# Function-Generator.net
KiCad netlist of a schematic drawn in Altium Designer
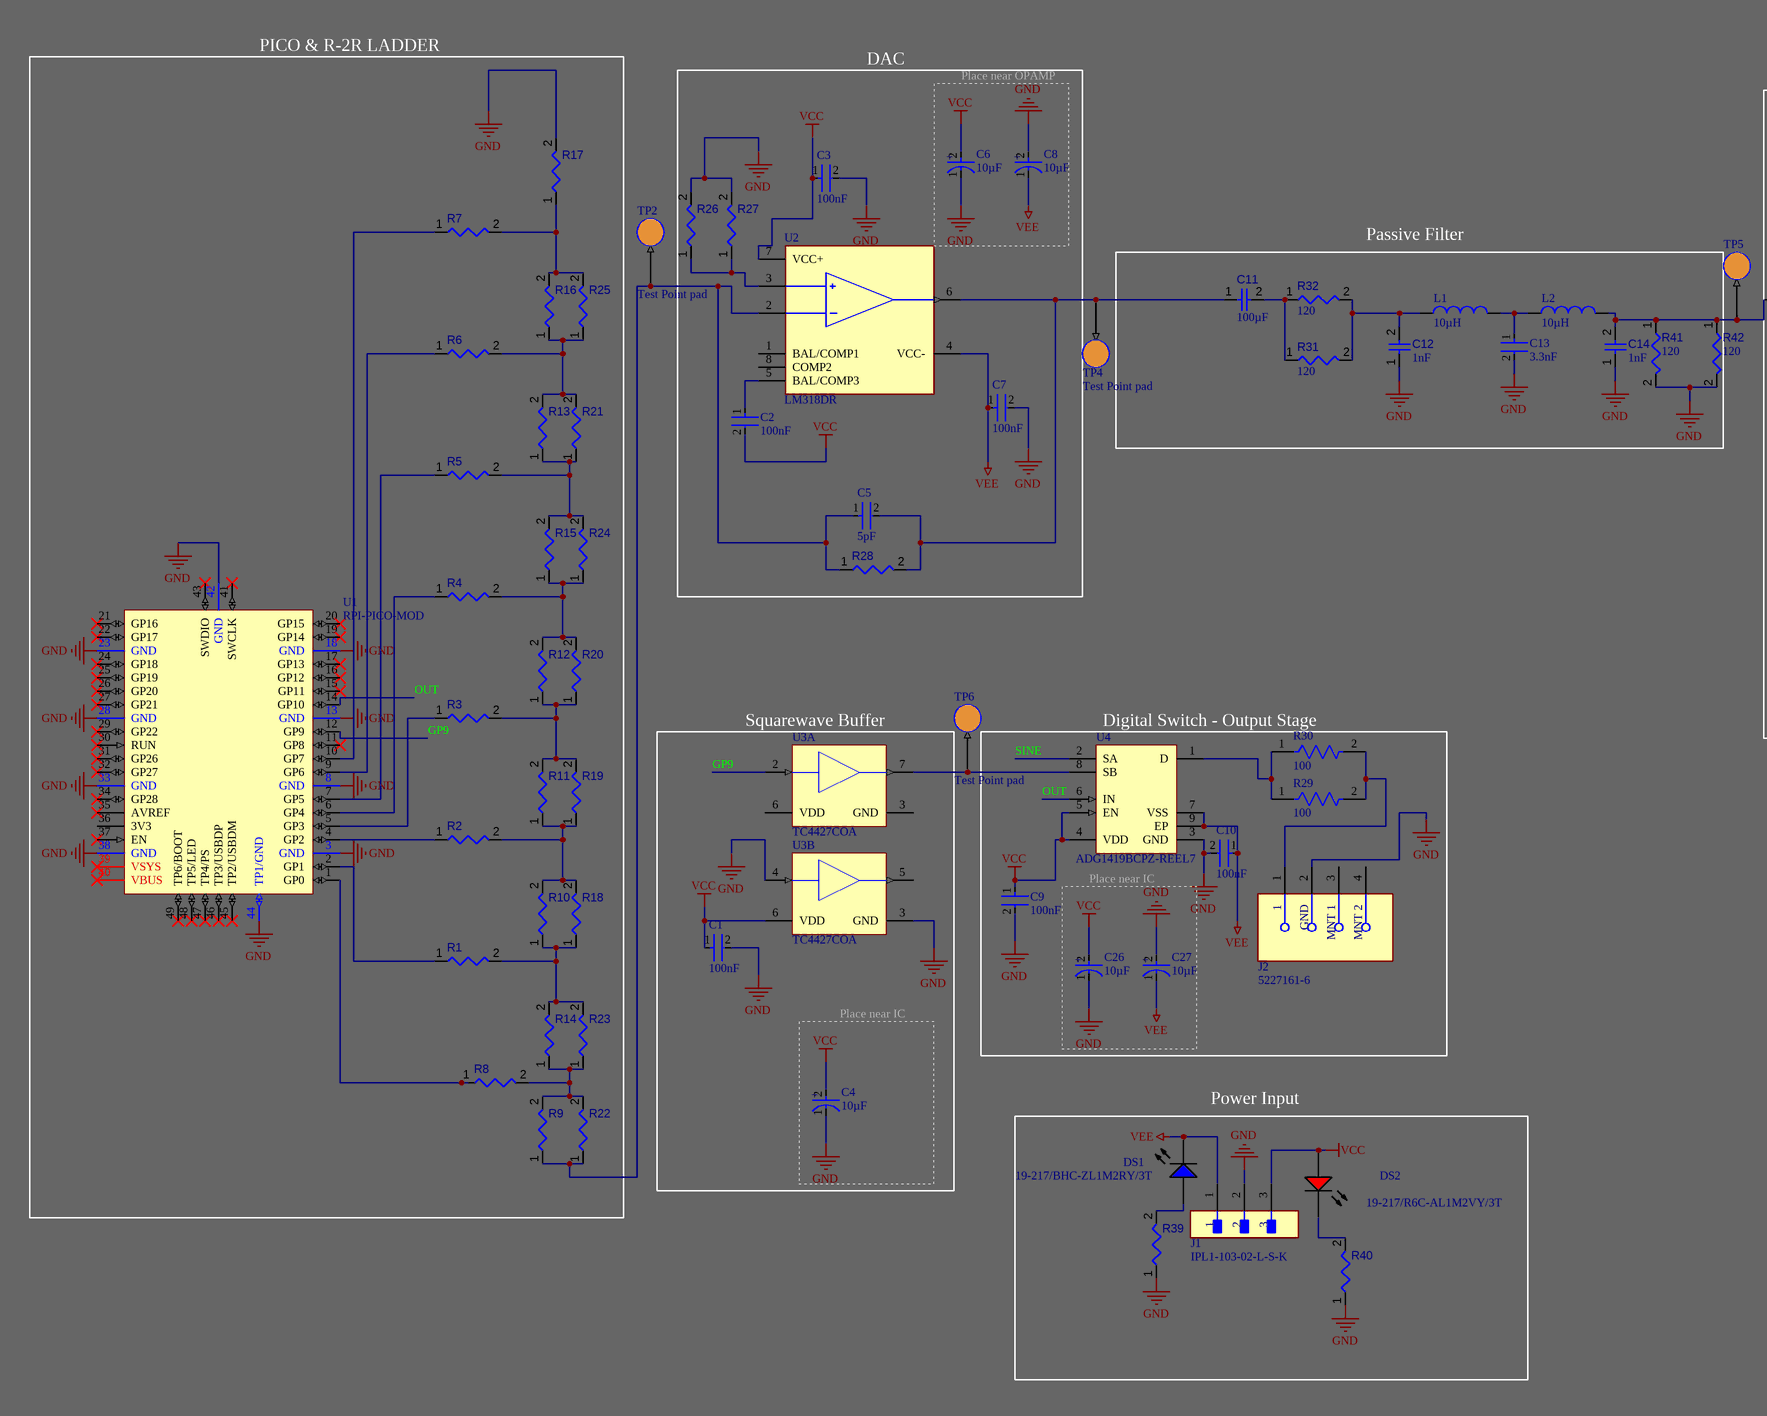
[diagram p0: Function-Generator.SchDoc, left]
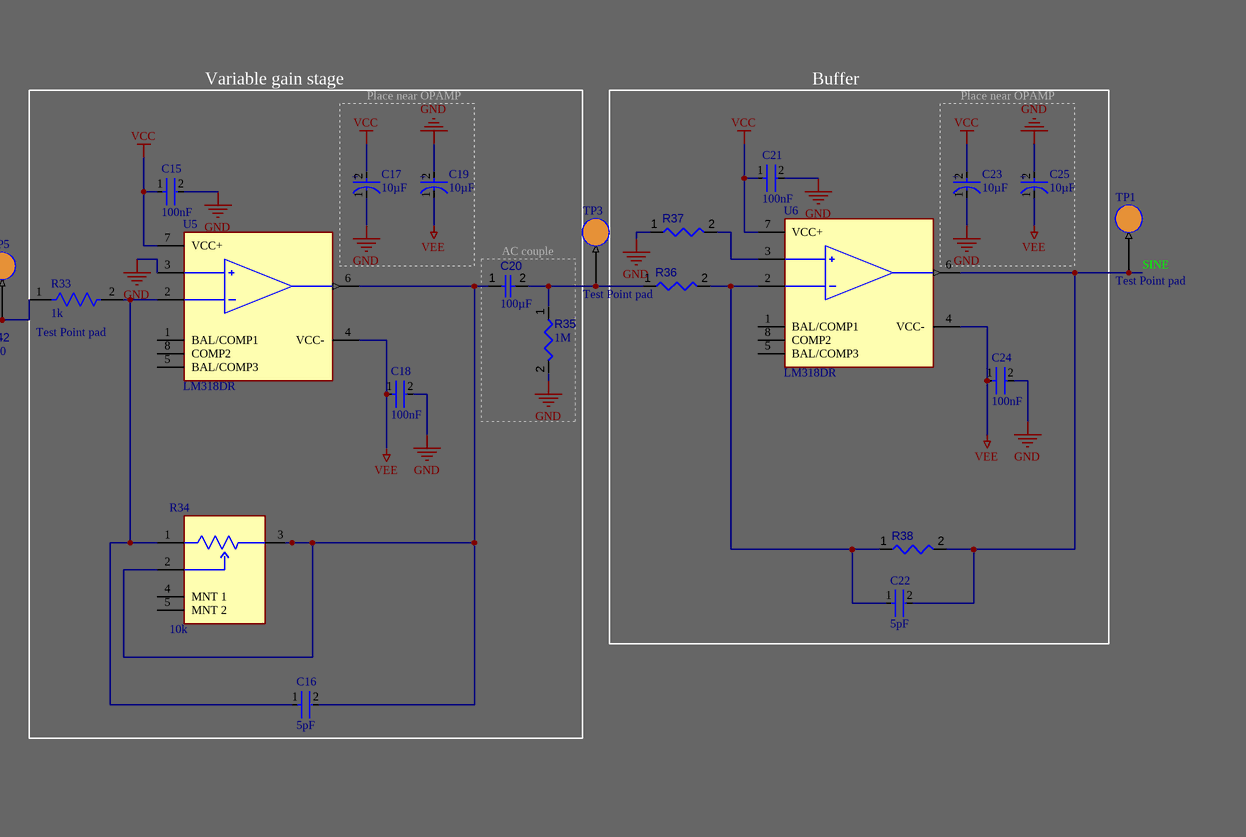
[diagram p1: Function-Generator.SchDoc, right]

(export (version "E")
  (design (tool "Eeschema 10.0.6"))
  (components
    (comp (ref "C1")
      (value "100nF")
      (footprint "FP-CC0805-0_85-IPC_A")
      (description "100V 100nF X7R 卤10% 0805 Multilayer Ceramic Capacitors MLCC - SMD/SMT ROHS")
      (fields (field (name "VOLTAGE") "25V") (field (name "TOLERANCE") "10%"))
      (libsource (lib "Lambros25") (part "11868f565c42a9108669ba33697ecf6"))
    )
    (comp (ref "C2")
      (value "100nF")
      (footprint "FP-CC0805-0_85-IPC_A")
      (description "100V 100nF X7R 卤10% 0805 Multilayer Ceramic Capacitors MLCC - SMD/SMT ROHS")
      (fields (field (name "VOLTAGE") "25V") (field (name "TOLERANCE") "10%"))
      (libsource (lib "Lambros25") (part "11868f565c42a9108669ba33697ecf6"))
    )
    (comp (ref "C3")
      (value "100nF")
      (footprint "FP-CC0805-0_85-IPC_A")
      (description "100V 100nF X7R 卤10% 0805 Multilayer Ceramic Capacitors MLCC - SMD/SMT ROHS")
      (fields (field (name "VOLTAGE") "25V") (field (name "TOLERANCE") "10%"))
      (libsource (lib "Lambros25") (part "11868f565c42a9108669ba33697ecf6"))
    )
    (comp (ref "C4")
      (value "10µF")
      (footprint "FP-FTB-MFG")
      (description "Radial Can - SMD ALUMINUM ELECTROLYTIC CAPACITOR FT 50V 10muF ±20% 0.157Dia 4.00mm")
      (fields (field (name "VOLTAGE") "50V") (field (name "TOLERANCE") "20%"))
      (libsource (lib "Lambros25") (part "a00bbbee19879c290e62620ae7e47b1"))
    )
    (comp (ref "C5")
      (value "5pF")
      (footprint "FP-GCH188-0_1-e0_2_0_5-IPC_A")
      (fields (field (name "JLCPCB PART #") "C1673") (field (name "Comment") "GCH1885C2A5R0CE01J"))
      (libsource (lib "Lambros25") (part "b4654b650e69147ec39a6b967a45e02"))
    )
    (comp (ref "C6")
      (value "10µF")
      (footprint "FP-FTB-MFG")
      (description "Radial Can - SMD ALUMINUM ELECTROLYTIC CAPACITOR FT 50V 10muF ±20% 0.157Dia 4.00mm")
      (fields (field (name "VOLTAGE") "50V") (field (name "TOLERANCE") "20%"))
      (libsource (lib "Lambros25") (part "a00bbbee19879c290e62620ae7e47b1"))
    )
    (comp (ref "C7")
      (value "100nF")
      (footprint "FP-CC0805-0_85-IPC_A")
      (description "100V 100nF X7R 卤10% 0805 Multilayer Ceramic Capacitors MLCC - SMD/SMT ROHS")
      (fields (field (name "VOLTAGE") "25V") (field (name "TOLERANCE") "10%"))
      (libsource (lib "Lambros25") (part "11868f565c42a9108669ba33697ecf6"))
    )
    (comp (ref "C8")
      (value "10µF")
      (footprint "FP-FTB-MFG")
      (description "Radial Can - SMD ALUMINUM ELECTROLYTIC CAPACITOR FT 50V 10muF ±20% 0.157Dia 4.00mm")
      (fields (field (name "VOLTAGE") "50V") (field (name "TOLERANCE") "20%"))
      (libsource (lib "Lambros25") (part "a00bbbee19879c290e62620ae7e47b1"))
    )
    (comp (ref "C9")
      (value "100nF")
      (footprint "FP-CC0805-0_85-IPC_A")
      (description "100V 100nF X7R 卤10% 0805 Multilayer Ceramic Capacitors MLCC - SMD/SMT ROHS")
      (fields (field (name "VOLTAGE") "25V") (field (name "TOLERANCE") "10%"))
      (libsource (lib "Lambros25") (part "11868f565c42a9108669ba33697ecf6"))
    )
    (comp (ref "C10")
      (value "100nF")
      (footprint "FP-CC0805-0_85-IPC_A")
      (description "100V 100nF X7R 卤10% 0805 Multilayer Ceramic Capacitors MLCC - SMD/SMT ROHS")
      (fields (field (name "VOLTAGE") "25V") (field (name "TOLERANCE") "10%"))
      (libsource (lib "Lambros25") (part "11868f565c42a9108669ba33697ecf6"))
    )
    (comp (ref "C11")
      (value "100µF")
      (footprint "CAPAE660650X800N")
      (description "Radial Can - SMD ALUMINUM ELECTROLYTIC CAPACITOR SEV 25V 100muF ±20% 0.248Dia 6.30mm")
      (fields (field (name "TOLERANCE") "20%") (field (name "JLCPCB PART #") "C3338"))
      (libsource (lib "Lambros25") (part "CAP-NP-2"))
    )
    (comp (ref "C12")
      (value "1nF")
      (footprint "Chip2PinSM127P600-8N")
      (description "1nF 50V C0G ±1% 0805 Multilayer Ceramic Capacitors MLCC - SMD/SMT ROHS")
      (fields (field (name "JLCPCB PART #") "C597356") (field (name "TOLERANCE") "10%"))
      (libsource (lib "Lambros25") (part "CAP-NP-2"))
    )
    (comp (ref "C13")
      (value "3.3nF")
      (footprint "FP-CL10-IPC_B")
      (description "50V 3.3nF C0G ±1% 0603 Multilayer Ceramic Capacitors MLCC - SMD/SMT ROHS")
      (fields (field (name "TOLERANCE") "1%") (field (name "VOLTAGE") "50V"))
      (libsource (lib "Lambros25") (part "02cd4be3c70576c341d710602a673aa"))
    )
    (comp (ref "C14")
      (value "1nF")
      (footprint "Chip2PinSM127P600-8N")
      (description "1nF 50V C0G ±1% 0805 Multilayer Ceramic Capacitors MLCC - SMD/SMT ROHS")
      (fields (field (name "JLCPCB PART #") "C597356") (field (name "TOLERANCE") "10%"))
      (libsource (lib "Lambros25") (part "CAP-NP-2"))
    )
    (comp (ref "C15")
      (value "100nF")
      (footprint "FP-CC0805-0_85-IPC_A")
      (description "100V 100nF X7R 卤10% 0805 Multilayer Ceramic Capacitors MLCC - SMD/SMT ROHS")
      (fields (field (name "VOLTAGE") "25V") (field (name "TOLERANCE") "10%"))
      (libsource (lib "Lambros25") (part "11868f565c42a9108669ba33697ecf6"))
    )
    (comp (ref "C16")
      (value "5pF")
      (footprint "FP-GCH188-0_1-e0_2_0_5-IPC_A")
      (fields (field (name "JLCPCB PART #") "C1673") (field (name "Comment") "GCH1885C2A5R0CE01J"))
      (libsource (lib "Lambros25") (part "b4654b650e69147ec39a6b967a45e02"))
    )
    (comp (ref "C17")
      (value "10µF")
      (footprint "FP-FTB-MFG")
      (description "Radial Can - SMD ALUMINUM ELECTROLYTIC CAPACITOR FT 50V 10muF ±20% 0.157Dia 4.00mm")
      (fields (field (name "VOLTAGE") "50V") (field (name "TOLERANCE") "20%"))
      (libsource (lib "Lambros25") (part "a00bbbee19879c290e62620ae7e47b1"))
    )
    (comp (ref "C18")
      (value "100nF")
      (footprint "FP-CC0805-0_85-IPC_A")
      (description "100V 100nF X7R 卤10% 0805 Multilayer Ceramic Capacitors MLCC - SMD/SMT ROHS")
      (fields (field (name "VOLTAGE") "25V") (field (name "TOLERANCE") "10%"))
      (libsource (lib "Lambros25") (part "11868f565c42a9108669ba33697ecf6"))
    )
    (comp (ref "C19")
      (value "10µF")
      (footprint "FP-FTB-MFG")
      (description "Radial Can - SMD ALUMINUM ELECTROLYTIC CAPACITOR FT 50V 10muF ±20% 0.157Dia 4.00mm")
      (fields (field (name "VOLTAGE") "50V") (field (name "TOLERANCE") "20%"))
      (libsource (lib "Lambros25") (part "a00bbbee19879c290e62620ae7e47b1"))
    )
    (comp (ref "C20")
      (value "100µF")
      (footprint "CAPAE660650X800N")
      (description "Radial Can - SMD ALUMINUM ELECTROLYTIC CAPACITOR SEV 25V 100muF ±20% 0.248Dia 6.30mm")
      (fields (field (name "TOLERANCE") "20%") (field (name "JLCPCB PART #") "C3338"))
      (libsource (lib "Lambros25") (part "CAP-NP-2"))
    )
    (comp (ref "C21")
      (value "100nF")
      (footprint "FP-CC0805-0_85-IPC_A")
      (description "100V 100nF X7R 卤10% 0805 Multilayer Ceramic Capacitors MLCC - SMD/SMT ROHS")
      (fields (field (name "VOLTAGE") "25V") (field (name "TOLERANCE") "10%"))
      (libsource (lib "Lambros25") (part "11868f565c42a9108669ba33697ecf6"))
    )
    (comp (ref "C22")
      (value "5pF")
      (footprint "FP-GCH188-0_1-e0_2_0_5-IPC_A")
      (fields (field (name "JLCPCB PART #") "C1673") (field (name "Comment") "GCH1885C2A5R0CE01J"))
      (libsource (lib "Lambros25") (part "b4654b650e69147ec39a6b967a45e02"))
    )
    (comp (ref "C23")
      (value "10µF")
      (footprint "FP-FTB-MFG")
      (description "Radial Can - SMD ALUMINUM ELECTROLYTIC CAPACITOR FT 50V 10muF ±20% 0.157Dia 4.00mm")
      (fields (field (name "VOLTAGE") "50V") (field (name "TOLERANCE") "20%"))
      (libsource (lib "Lambros25") (part "a00bbbee19879c290e62620ae7e47b1"))
    )
    (comp (ref "C24")
      (value "100nF")
      (footprint "FP-CC0805-0_85-IPC_A")
      (description "100V 100nF X7R 卤10% 0805 Multilayer Ceramic Capacitors MLCC - SMD/SMT ROHS")
      (fields (field (name "VOLTAGE") "25V") (field (name "TOLERANCE") "10%"))
      (libsource (lib "Lambros25") (part "11868f565c42a9108669ba33697ecf6"))
    )
    (comp (ref "C25")
      (value "10µF")
      (footprint "FP-FTB-MFG")
      (description "Radial Can - SMD ALUMINUM ELECTROLYTIC CAPACITOR FT 50V 10muF ±20% 0.157Dia 4.00mm")
      (fields (field (name "VOLTAGE") "50V") (field (name "TOLERANCE") "20%"))
      (libsource (lib "Lambros25") (part "a00bbbee19879c290e62620ae7e47b1"))
    )
    (comp (ref "C26")
      (value "10µF")
      (footprint "FP-FTB-MFG")
      (description "Radial Can - SMD ALUMINUM ELECTROLYTIC CAPACITOR FT 50V 10muF ±20% 0.157Dia 4.00mm")
      (fields (field (name "VOLTAGE") "50V") (field (name "TOLERANCE") "20%"))
      (libsource (lib "Lambros25") (part "a00bbbee19879c290e62620ae7e47b1"))
    )
    (comp (ref "C27")
      (value "10µF")
      (footprint "FP-FTB-MFG")
      (description "Radial Can - SMD ALUMINUM ELECTROLYTIC CAPACITOR FT 50V 10muF ±20% 0.157Dia 4.00mm")
      (fields (field (name "VOLTAGE") "50V") (field (name "TOLERANCE") "20%"))
      (libsource (lib "Lambros25") (part "a00bbbee19879c290e62620ae7e47b1"))
    )
    (comp (ref "DS1")
      (value "19-217/BHC-ZL1M2RY/3T")
      (footprint "EVRL-0603-2_V")
      (description "Chip LED, Blue, 5 V, 25 mA, -40 to 85 degC, 2-Pin SMD (0603), RoHS, Tape and Reel")
      (fields (field (name "MANUFACTURER") "Everlight Electronics") (field (name "JLCPCB PART #") "C2288"))
      (libsource (lib "Lambros25") (part "LED-BLUE-AK-2"))
    )
    (comp (ref "DS2")
      (value "19-217/R6C-AL1M2VY/3T")
      (footprint "EVRL-0603-2_V")
      (description "Chip LED, Red, 5 V, 25 mA, -40 to 85 degC, 2-Pin SMD (0603), RoHS, Tape and Reel")
      (fields (field (name "MANUFACTURER") "Everlight Electronics") (field (name "JLCPCB PART #") "C2286"))
      (libsource (lib "Lambros25") (part "LED-RED-AK-2"))
    )
    (comp (ref "J1")
      (value "IPL1-103-02-L-S-K")
      (footprint "FP-IPL1-103-02-L-S-K-0")
      (description "Samtec 2.54mmpitch3pSingle row pin header, IPL1series, right angle, surface")
      (fields (field (name "JLCPCB PART #") "C3326049"))
      (libsource (lib "Lambros25") (part "044adefd6287a37253661db429b75cc"))
    )
    (comp (ref "J2")
      (value "5227161-6")
      (footprint "FP-5227161-6-MFG")
      (description "RF / Coaxial Connector, BNC Coaxial, Right Angle Jack, Solder, 50 ohm, Phosphor Bronze")
      (fields (field (name "JLCPCB PART #") "C5166169"))
      (libsource (lib "Lambros25") (part "5e99626469102f53c3612a7d572d391"))
    )
    (comp (ref "L1")
      (value "10µH")
      (footprint "Chip2PinSM127P600-8N")
      (description "SDFL1608S100KTF, 10uH, 10%, 1 Element, Ferrite-Core, SMD, 0603")
      (fields (field (name "TOLERANCE") "10%") (field (name "JLCPCB PART #") "C1035"))
      (libsource (lib "Lambros25") (part "IND-2"))
    )
    (comp (ref "L2")
      (value "10µH")
      (footprint "Chip2PinSM127P600-8N")
      (description "SDFL1608S100KTF, 10uH, 10%, 1 Element, Ferrite-Core, SMD, 0603")
      (fields (field (name "TOLERANCE") "10%") (field (name "JLCPCB PART #") "C1035"))
      (libsource (lib "Lambros25") (part "IND-2"))
    )
    (comp (ref "R1")
      (value "0805W8F2201T5E")
      (footprint "Chip2PinSM127P600-8N")
      (description "chip resistor 2200Ω ±1% 1/8W 0805")
      (fields (field (name "JLCPCB PART #") "C17520"))
      (libsource (lib "Lambros25") (part "RES-2"))
    )
    (comp (ref "R2")
      (value "0805W8F2201T5E")
      (footprint "Chip2PinSM127P600-8N")
      (description "chip resistor 2200Ω ±1% 1/8W 0805")
      (fields (field (name "JLCPCB PART #") "C17520"))
      (libsource (lib "Lambros25") (part "RES-2"))
    )
    (comp (ref "R3")
      (value "0805W8F2201T5E")
      (footprint "Chip2PinSM127P600-8N")
      (description "chip resistor 2200Ω ±1% 1/8W 0805")
      (fields (field (name "JLCPCB PART #") "C17520"))
      (libsource (lib "Lambros25") (part "RES-2"))
    )
    (comp (ref "R4")
      (value "0805W8F2201T5E")
      (footprint "Chip2PinSM127P600-8N")
      (description "chip resistor 2200Ω ±1% 1/8W 0805")
      (fields (field (name "JLCPCB PART #") "C17520"))
      (libsource (lib "Lambros25") (part "RES-2"))
    )
    (comp (ref "R5")
      (value "0805W8F2201T5E")
      (footprint "Chip2PinSM127P600-8N")
      (description "chip resistor 2200Ω ±1% 1/8W 0805")
      (fields (field (name "JLCPCB PART #") "C17520"))
      (libsource (lib "Lambros25") (part "RES-2"))
    )
    (comp (ref "R6")
      (value "0805W8F2201T5E")
      (footprint "Chip2PinSM127P600-8N")
      (description "chip resistor 2200Ω ±1% 1/8W 0805")
      (fields (field (name "JLCPCB PART #") "C17520"))
      (libsource (lib "Lambros25") (part "RES-2"))
    )
    (comp (ref "R7")
      (value "0805W8F2201T5E")
      (footprint "Chip2PinSM127P600-8N")
      (description "chip resistor 2200Ω ±1% 1/8W 0805")
      (fields (field (name "JLCPCB PART #") "C17520"))
      (libsource (lib "Lambros25") (part "RES-2"))
    )
    (comp (ref "R8")
      (value "0805W8F2201T5E")
      (footprint "Chip2PinSM127P600-8N")
      (description "chip resistor 2200Ω ±1% 1/8W 0805")
      (fields (field (name "JLCPCB PART #") "C17520"))
      (libsource (lib "Lambros25") (part "RES-2"))
    )
    (comp (ref "R9")
      (value "0805W8F2201T5E")
      (footprint "Chip2PinSM127P600-8N")
      (description "chip resistor 2200Ω ±1% 1/8W 0805")
      (fields (field (name "JLCPCB PART #") "C17520"))
      (libsource (lib "Lambros25") (part "RES-2"))
    )
    (comp (ref "R10")
      (value "0805W8F2201T5E")
      (footprint "Chip2PinSM127P600-8N")
      (description "chip resistor 2200Ω ±1% 1/8W 0805")
      (fields (field (name "JLCPCB PART #") "C17520"))
      (libsource (lib "Lambros25") (part "RES-2"))
    )
    (comp (ref "R11")
      (value "0805W8F2201T5E")
      (footprint "Chip2PinSM127P600-8N")
      (description "chip resistor 2200Ω ±1% 1/8W 0805")
      (fields (field (name "JLCPCB PART #") "C17520"))
      (libsource (lib "Lambros25") (part "RES-2"))
    )
    (comp (ref "R12")
      (value "0805W8F2201T5E")
      (footprint "Chip2PinSM127P600-8N")
      (description "chip resistor 2200Ω ±1% 1/8W 0805")
      (fields (field (name "JLCPCB PART #") "C17520"))
      (libsource (lib "Lambros25") (part "RES-2"))
    )
    (comp (ref "R13")
      (value "0805W8F2201T5E")
      (footprint "Chip2PinSM127P600-8N")
      (description "chip resistor 2200Ω ±1% 1/8W 0805")
      (fields (field (name "JLCPCB PART #") "C17520"))
      (libsource (lib "Lambros25") (part "RES-2"))
    )
    (comp (ref "R14")
      (value "0805W8F2201T5E")
      (footprint "Chip2PinSM127P600-8N")
      (description "chip resistor 2200Ω ±1% 1/8W 0805")
      (fields (field (name "JLCPCB PART #") "C17520"))
      (libsource (lib "Lambros25") (part "RES-2"))
    )
    (comp (ref "R15")
      (value "0805W8F2201T5E")
      (footprint "Chip2PinSM127P600-8N")
      (description "chip resistor 2200Ω ±1% 1/8W 0805")
      (fields (field (name "JLCPCB PART #") "C17520"))
      (libsource (lib "Lambros25") (part "RES-2"))
    )
    (comp (ref "R16")
      (value "0805W8F2201T5E")
      (footprint "Chip2PinSM127P600-8N")
      (description "chip resistor 2200Ω ±1% 1/8W 0805")
      (fields (field (name "JLCPCB PART #") "C17520"))
      (libsource (lib "Lambros25") (part "RES-2"))
    )
    (comp (ref "R17")
      (value "0805W8F2201T5E")
      (footprint "Chip2PinSM127P600-8N")
      (description "chip resistor 2200Ω ±1% 1/8W 0805")
      (fields (field (name "JLCPCB PART #") "C17520"))
      (libsource (lib "Lambros25") (part "RES-2"))
    )
    (comp (ref "R18")
      (value "0805W8F2201T5E")
      (footprint "Chip2PinSM127P600-8N")
      (description "chip resistor 2200Ω ±1% 1/8W 0805")
      (fields (field (name "JLCPCB PART #") "C17520"))
      (libsource (lib "Lambros25") (part "RES-2"))
    )
    (comp (ref "R19")
      (value "0805W8F2201T5E")
      (footprint "Chip2PinSM127P600-8N")
      (description "chip resistor 2200Ω ±1% 1/8W 0805")
      (fields (field (name "JLCPCB PART #") "C17520"))
      (libsource (lib "Lambros25") (part "RES-2"))
    )
    (comp (ref "R20")
      (value "0805W8F2201T5E")
      (footprint "Chip2PinSM127P600-8N")
      (description "chip resistor 2200Ω ±1% 1/8W 0805")
      (fields (field (name "JLCPCB PART #") "C17520"))
      (libsource (lib "Lambros25") (part "RES-2"))
    )
    (comp (ref "R21")
      (value "0805W8F2201T5E")
      (footprint "Chip2PinSM127P600-8N")
      (description "chip resistor 2200Ω ±1% 1/8W 0805")
      (fields (field (name "JLCPCB PART #") "C17520"))
      (libsource (lib "Lambros25") (part "RES-2"))
    )
    (comp (ref "R22")
      (value "0805W8F2201T5E")
      (footprint "Chip2PinSM127P600-8N")
      (description "chip resistor 2200Ω ±1% 1/8W 0805")
      (fields (field (name "JLCPCB PART #") "C17520"))
      (libsource (lib "Lambros25") (part "RES-2"))
    )
    (comp (ref "R23")
      (value "0805W8F2201T5E")
      (footprint "Chip2PinSM127P600-8N")
      (description "chip resistor 2200Ω ±1% 1/8W 0805")
      (fields (field (name "JLCPCB PART #") "C17520"))
      (libsource (lib "Lambros25") (part "RES-2"))
    )
    (comp (ref "R24")
      (value "0805W8F2201T5E")
      (footprint "Chip2PinSM127P600-8N")
      (description "chip resistor 2200Ω ±1% 1/8W 0805")
      (fields (field (name "JLCPCB PART #") "C17520"))
      (libsource (lib "Lambros25") (part "RES-2"))
    )
    (comp (ref "R25")
      (value "0805W8F2201T5E")
      (footprint "Chip2PinSM127P600-8N")
      (description "chip resistor 2200Ω ±1% 1/8W 0805")
      (fields (field (name "JLCPCB PART #") "C17520"))
      (libsource (lib "Lambros25") (part "RES-2"))
    )
    (comp (ref "R26")
      (value "0805W8F2201T5E")
      (footprint "Chip2PinSM127P600-8N")
      (description "chip resistor 2200Ω ±1% 1/8W 0805")
      (fields (field (name "JLCPCB PART #") "C17520"))
      (libsource (lib "Lambros25") (part "RES-2"))
    )
    (comp (ref "R27")
      (value "0805W8F2201T5E")
      (footprint "Chip2PinSM127P600-8N")
      (description "chip resistor 2200Ω ±1% 1/8W 0805")
      (fields (field (name "JLCPCB PART #") "C17520"))
      (libsource (lib "Lambros25") (part "RES-2"))
    )
    (comp (ref "R28")
      (value "0805W8F2201T5E")
      (footprint "Chip2PinSM127P600-8N")
      (description "chip resistor 2200Ω ±1% 1/8W 0805")
      (fields (field (name "JLCPCB PART #") "C17520"))
      (libsource (lib "Lambros25") (part "RES-2"))
    )
    (comp (ref "R29")
      (value "100")
      (footprint "FP-SR0805-MFG")
      (description "125mW Thick Film Resistors 150V ±100ppm/℃ ±1% 100Ω 0805 Chip Resistor - Surface Mount ROHS")
      (fields (field (name "TOLERANCE") "1%") (field (name "JLCPCB PART #") "C17408"))
      (libsource (lib "Lambros25") (part "1029c3af85768c4190bb7ad29bc67b5"))
    )
    (comp (ref "R30")
      (value "100")
      (footprint "FP-SR0805-MFG")
      (description "125mW Thick Film Resistors 150V ±100ppm/℃ ±1% 100Ω 0805 Chip Resistor - Surface Mount ROHS")
      (fields (field (name "TOLERANCE") "1%") (field (name "JLCPCB PART #") "C17408"))
      (libsource (lib "Lambros25") (part "1029c3af85768c4190bb7ad29bc67b5"))
    )
    (comp (ref "R31")
      (value "120")
      (footprint "Chip2PinSM127P600-8N")
      (description "Res Thick Film 0805 120 Ohm 1% 0.125W(1/8W) ±100ppm/C Pad SMD T/R")
      (fields (field (name "JLCPCB PART #") "C17437") (field (name "Comment") "0805W8F1200T5E"))
      (libsource (lib "Lambros25") (part "RES-2"))
    )
    (comp (ref "R32")
      (value "120")
      (footprint "Chip2PinSM127P600-8N")
      (description "Res Thick Film 0805 120 Ohm 1% 0.125W(1/8W) ±100ppm/C Pad SMD T/R")
      (fields (field (name "JLCPCB PART #") "C17437") (field (name "Comment") "0805W8F1200T5E"))
      (libsource (lib "Lambros25") (part "RES-2"))
    )
    (comp (ref "R33")
      (value "1k")
      (footprint "FP-ERA6A-IPC_B")
      (description "Res Thin Film 0805 1K Ohm 0.1% 0.125W ±10ppm/°C Molded SMD Punched Carrier T/R")
      (fields (field (name "TOLERANCE") "0.1%") (field (name "JCLPCB PART #") "C17513"))
      (libsource (lib "Lambros25") (part "1029c3af85768c4190bb7ad29bc67b5"))
    )
    (comp (ref "R34")
      (value "10k")
      (footprint "FP-RK09L1140A2U-MFG")
      (description "10k Ohm 1 Gang Linear Through Hole Potentiometer 1.0 Turns 0.05W, 1/20W PC Pins")
      (fields (field (name "TOLERANCE") "20%") (field (name "JLCPCB PART #") "C470448"))
      (libsource (lib "Lambros25") (part "0c568a6e0ac31b8b52ae5f6704acd43"))
    )
    (comp (ref "R35")
      (value "1M")
      (footprint "Chip2PinSM127P600-8N")
      (description "Res Thick Film 0805 1M Ohm 1% 0.125W(1/8W) ±100ppm/C Pad SMD T/R")
      (fields (field (name "JLCPCB PART #") "C17514") (field (name "Comment") "0805W8F1004T5E"))
      (libsource (lib "Lambros25") (part "RES-2"))
    )
    (comp (ref "R36")
      (value "0805W8F2201T5E")
      (footprint "Chip2PinSM127P600-8N")
      (description "chip resistor 2200Ω ±1% 1/8W 0805")
      (fields (field (name "JLCPCB PART #") "C17520"))
      (libsource (lib "Lambros25") (part "RES-2"))
    )
    (comp (ref "R37")
      (value "0805W8F2201T5E")
      (footprint "Chip2PinSM127P600-8N")
      (description "chip resistor 2200Ω ±1% 1/8W 0805")
      (fields (field (name "JLCPCB PART #") "C17520"))
      (libsource (lib "Lambros25") (part "RES-2"))
    )
    (comp (ref "R38")
      (value "0805W8F2201T5E")
      (footprint "Chip2PinSM127P600-8N")
      (description "chip resistor 2200Ω ±1% 1/8W 0805")
      (fields (field (name "JLCPCB PART #") "C17520"))
      (libsource (lib "Lambros25") (part "RES-2"))
    )
    (comp (ref "R39")
      (value "0805W8F2201T5E")
      (footprint "Chip2PinSM127P600-8N")
      (description "chip resistor 2200Ω ±1% 1/8W 0805")
      (fields (field (name "JLCPCB PART #") "C17520"))
      (libsource (lib "Lambros25") (part "RES-2"))
    )
    (comp (ref "R40")
      (value "0805W8F2201T5E")
      (footprint "Chip2PinSM127P600-8N")
      (description "chip resistor 2200Ω ±1% 1/8W 0805")
      (fields (field (name "JLCPCB PART #") "C17520"))
      (libsource (lib "Lambros25") (part "RES-2"))
    )
    (comp (ref "R41")
      (value "120")
      (footprint "Chip2PinSM127P600-8N")
      (description "Res Thick Film 0805 120 Ohm 1% 0.125W(1/8W) ±100ppm/C Pad SMD T/R")
      (fields (field (name "JLCPCB PART #") "C17437") (field (name "Comment") "0805W8F1200T5E"))
      (libsource (lib "Lambros25") (part "RES-2"))
    )
    (comp (ref "R42")
      (value "120")
      (footprint "Chip2PinSM127P600-8N")
      (description "Res Thick Film 0805 120 Ohm 1% 0.125W(1/8W) ±100ppm/C Pad SMD T/R")
      (fields (field (name "JLCPCB PART #") "C17437") (field (name "Comment") "0805W8F1200T5E"))
      (libsource (lib "Lambros25") (part "RES-2"))
    )
    (comp (ref "TP1")
      (value "Test Point pad")
      (footprint "TestPointPad-2mm")
      (libsource (lib "Lambros25") (part "TestPoint 2mm"))
    )
    (comp (ref "TP2")
      (value "Test Point pad")
      (footprint "TestPointPad-2mm")
      (libsource (lib "Lambros25") (part "TestPoint 2mm"))
    )
    (comp (ref "TP3")
      (value "Test Point pad")
      (footprint "TestPointPad-2mm")
      (libsource (lib "Lambros25") (part "TestPoint 2mm"))
    )
    (comp (ref "TP4")
      (value "Test Point pad")
      (footprint "TestPointPad-2mm")
      (libsource (lib "Lambros25") (part "TestPoint 2mm"))
    )
    (comp (ref "TP5")
      (value "Test Point pad")
      (footprint "TestPointPad-2mm")
      (libsource (lib "Lambros25") (part "TestPoint 2mm"))
    )
    (comp (ref "TP6")
      (value "Test Point pad")
      (footprint "TestPointPad-2mm")
      (libsource (lib "Lambros25") (part "TestPoint 2mm"))
    )
    (comp (ref "U1")
      (value "RPI-PICO-MOD")
      (footprint "RPI-PICO-MOD")
      (description "RASPBERRY PI PICO RP2040 BOARD")
      (fields
        (field (name "MANUFACTURER") "Raspberry Pi Foundation")
        (field (name "MANUFACTURER PART NO") "SC0915")
      )
      (libsource (lib "Lambros25") (part "RPI-PICO-MOD"))
    )
    (comp (ref "U2")
      (value "LM318DR")
      (footprint "FP-D0008A-IPC_B")
      (description "Single, 40-V, 15-MHz operational amplifier 8-SOIC 0 to 70")
      (fields (field (name "JCLPCB PART #") "C2871089") (field (name "JLCPCB PART #") "C1347395"))
      (libsource (lib "Lambros25") (part "ba81798d5a184761be58ef4be7d9477"))
    )
    (comp (ref "U3")
      (value "TC4427COA")
      (footprint "SOIC-OA8_L")
      (description "TC4427COA; Dual MOSFET Power Driver 1.5A; 4.5 to 18V; Non-Inverting; 8-Pin SOIC")
      (fields (field (name "JLCPCB PART #") "C636890"))
      (libsource (lib "Lambros25") (part "IN-MOSDRV-TC1427CPA-8"))
    )
    (comp (ref "U4")
      (value "ADG1419BCPZ-REEL7")
      (footprint "ADI-CP-8-4_V")
      (description "Other Interface ICs; ADG1419BCPZ-REEL7; ANALOG DEVICES; 8; 16.5 V; 5 V; LFCSP EP")
      (fields (field (name "JLCPCB PART #") "C206632"))
      (libsource (lib "Lambros25") (part "ADI-ADG1419-CP-8-4"))
    )
    (comp (ref "U5")
      (value "LM318DR")
      (footprint "FP-D0008A-IPC_B")
      (description "Single, 40-V, 15-MHz operational amplifier 8-SOIC 0 to 70")
      (fields (field (name "JCLPCB PART #") "C2871089") (field (name "JLCPCB PART #") "C1347395"))
      (libsource (lib "Lambros25") (part "ba81798d5a184761be58ef4be7d9477"))
    )
    (comp (ref "U6")
      (value "LM318DR")
      (footprint "FP-D0008A-IPC_B")
      (description "Single, 40-V, 15-MHz operational amplifier 8-SOIC 0 to 70")
      (fields (field (name "JCLPCB PART #") "C2871089") (field (name "JLCPCB PART #") "C1347395"))
      (libsource (lib "Lambros25") (part "ba81798d5a184761be58ef4be7d9477"))
    )
  )
  (nets
    (net (code "1") (name "/GP9") (class "Default")
      (node (ref "U1") (pin "12") (pinfunction "GP9_12") (pintype "bidirectional"))
      (node (ref "U3") (pin "2") (pinfunction "INA_2") (pintype "input"))
    )
    (net (code "2") (name "/OUT") (class "Default")
      (node (ref "U1") (pin "14") (pinfunction "GP10_14") (pintype "bidirectional"))
      (node (ref "U4") (pin "6") (pinfunction "IN_6") (pintype "input"))
    )
    (net (code "3") (name "/SINE") (class "Default")
      (node (ref "C22") (pin "2") (pinfunction "2_2") (pintype "passive"))
      (node (ref "R38") (pin "2") (pinfunction "2_2") (pintype "passive"))
      (node (ref "TP1") (pin "1") (pintype "input"))
      (node (ref "U4") (pin "2") (pinfunction "SA_2") (pintype "passive"))
      (node (ref "U6") (pin "6") (pinfunction "OUT_6") (pintype "output"))
    )
    (net (code "4") (name "GND") (class "Default")
      (node (ref "C1") (pin "2") (pinfunction "2_2") (pintype "passive"))
      (node (ref "C10") (pin "2") (pinfunction "2_2") (pintype "passive"))
      (node (ref "C12") (pin "1") (pinfunction "1_1") (pintype "passive"))
      (node (ref "C13") (pin "2") (pinfunction "2_2") (pintype "passive"))
      (node (ref "C14") (pin "1") (pinfunction "1_1") (pintype "passive"))
      (node (ref "C15") (pin "2") (pinfunction "2_2") (pintype "passive"))
      (node (ref "C17") (pin "1") (pinfunction "C_1") (pintype "passive"))
      (node (ref "C18") (pin "2") (pinfunction "2_2") (pintype "passive"))
      (node (ref "C19") (pin "2") (pinfunction "A_2") (pintype "passive"))
      (node (ref "C21") (pin "2") (pinfunction "2_2") (pintype "passive"))
      (node (ref "C23") (pin "1") (pinfunction "C_1") (pintype "passive"))
      (node (ref "C24") (pin "2") (pinfunction "2_2") (pintype "passive"))
      (node (ref "C25") (pin "2") (pinfunction "A_2") (pintype "passive"))
      (node (ref "C26") (pin "1") (pinfunction "C_1") (pintype "passive"))
      (node (ref "C27") (pin "2") (pinfunction "A_2") (pintype "passive"))
      (node (ref "C3") (pin "2") (pinfunction "2_2") (pintype "passive"))
      (node (ref "C4") (pin "1") (pinfunction "C_1") (pintype "passive"))
      (node (ref "C6") (pin "1") (pinfunction "C_1") (pintype "passive"))
      (node (ref "C7") (pin "2") (pinfunction "2_2") (pintype "passive"))
      (node (ref "C8") (pin "2") (pinfunction "A_2") (pintype "passive"))
      (node (ref "C9") (pin "2") (pinfunction "2_2") (pintype "passive"))
      (node (ref "J1") (pin "2") (pinfunction "2_2") (pintype "passive"))
      (node (ref "J2") (pin "2") (pinfunction "GND_2") (pintype "passive"))
      (node (ref "R17") (pin "2") (pinfunction "2_2") (pintype "passive"))
      (node (ref "R26") (pin "2") (pinfunction "2_2") (pintype "passive"))
      (node (ref "R27") (pin "2") (pinfunction "2_2") (pintype "passive"))
      (node (ref "R35") (pin "2") (pinfunction "2_2") (pintype "passive"))
      (node (ref "R37") (pin "1") (pinfunction "1_1") (pintype "passive"))
      (node (ref "R39") (pin "1") (pinfunction "1_1") (pintype "passive"))
      (node (ref "R40") (pin "1") (pinfunction "1_1") (pintype "passive"))
      (node (ref "R41") (pin "2") (pinfunction "2_2") (pintype "passive"))
      (node (ref "R42") (pin "2") (pinfunction "2_2") (pintype "passive"))
      (node (ref "U1") (pin "13") (pinfunction "GND_13") (pintype "power_in"))
      (node (ref "U1") (pin "18") (pinfunction "GND_18") (pintype "power_in"))
      (node (ref "U1") (pin "23") (pinfunction "GND_23") (pintype "power_in"))
      (node (ref "U1") (pin "28") (pinfunction "GND_28") (pintype "power_in"))
      (node (ref "U1") (pin "3") (pinfunction "GND_3") (pintype "power_in"))
      (node (ref "U1") (pin "33") (pinfunction "GND_33") (pintype "power_in"))
      (node (ref "U1") (pin "38") (pinfunction "GND_38") (pintype "power_in"))
      (node (ref "U1") (pin "42") (pinfunction "GND_42") (pintype "power_in"))
      (node (ref "U1") (pin "44") (pinfunction "TP1/GND_44") (pintype "bidirectional"))
      (node (ref "U1") (pin "8") (pinfunction "GND_8") (pintype "power_in"))
      (node (ref "U3") (pin "3") (pinfunction "GND_3") (pintype "power_in"))
      (node (ref "U3") (pin "4") (pinfunction "INB_4") (pintype "input"))
      (node (ref "U4") (pin "3") (pinfunction "GND_3") (pintype "power_in"))
      (node (ref "U5") (pin "3") (pinfunction "IN+_3") (pintype "tri_state"))
    )
    (net (code "5") (name "Net-(C11-Pad2)") (class "Default")
      (node (ref "C11") (pin "2") (pinfunction "2_2") (pintype "passive"))
      (node (ref "R31") (pin "1") (pinfunction "1_1") (pintype "passive"))
      (node (ref "R32") (pin "1") (pinfunction "1_1") (pintype "passive"))
    )
    (net (code "6") (name "Net-(C12-Pad2)") (class "Default")
      (node (ref "C12") (pin "2") (pinfunction "2_2") (pintype "passive"))
      (node (ref "L1") (pin "1") (pinfunction "1_1") (pintype "passive"))
      (node (ref "R31") (pin "2") (pinfunction "2_2") (pintype "passive"))
      (node (ref "R32") (pin "2") (pinfunction "2_2") (pintype "passive"))
    )
    (net (code "7") (name "Net-(C13-Pad1)") (class "Default")
      (node (ref "C13") (pin "1") (pinfunction "1_1") (pintype "passive"))
      (node (ref "L1") (pin "2") (pinfunction "2_2") (pintype "passive"))
      (node (ref "L2") (pin "1") (pinfunction "1_1") (pintype "passive"))
    )
    (net (code "8") (name "Net-(C14-Pad2)") (class "Default")
      (node (ref "C14") (pin "2") (pinfunction "2_2") (pintype "passive"))
      (node (ref "L2") (pin "2") (pinfunction "2_2") (pintype "passive"))
      (node (ref "R33") (pin "1") (pinfunction "1_1") (pintype "passive"))
      (node (ref "R41") (pin "1") (pinfunction "1_1") (pintype "passive"))
      (node (ref "R42") (pin "1") (pinfunction "1_1") (pintype "passive"))
      (node (ref "TP5") (pin "1") (pintype "input"))
    )
    (net (code "9") (name "Net-(C20-Pad2)") (class "Default")
      (node (ref "C20") (pin "2") (pinfunction "2_2") (pintype "passive"))
      (node (ref "R35") (pin "1") (pinfunction "1_1") (pintype "passive"))
      (node (ref "R36") (pin "1") (pinfunction "1_1") (pintype "passive"))
      (node (ref "TP3") (pin "1") (pintype "input"))
    )
    (net (code "10") (name "Net-(DS1-A)") (class "Default")
      (node (ref "DS1") (pin "1") (pinfunction "A_1") (pintype "passive"))
      (node (ref "R39") (pin "2") (pinfunction "2_2") (pintype "passive"))
    )
    (net (code "11") (name "Net-(DS2-K)") (class "Default")
      (node (ref "DS2") (pin "2") (pinfunction "K_2") (pintype "passive"))
      (node (ref "R40") (pin "2") (pinfunction "2_2") (pintype "passive"))
    )
    (net (code "12") (name "Net-(J2-Pad1)") (class "Default")
      (node (ref "J2") (pin "1") (pinfunction "1_1") (pintype "passive"))
      (node (ref "R29") (pin "2") (pinfunction "2_2") (pintype "passive"))
      (node (ref "R30") (pin "2") (pinfunction "2_2") (pintype "passive"))
    )
    (net (code "13") (name "Net-(R1-Pad2)") (class "Default")
      (node (ref "R1") (pin "2") (pinfunction "2_2") (pintype "passive"))
      (node (ref "R10") (pin "1") (pinfunction "1_1") (pintype "passive"))
      (node (ref "R14") (pin "2") (pinfunction "2_2") (pintype "passive"))
      (node (ref "R18") (pin "1") (pinfunction "1_1") (pintype "passive"))
      (node (ref "R23") (pin "2") (pinfunction "2_2") (pintype "passive"))
    )
    (net (code "14") (name "Net-(R10-Pad2)") (class "Default")
      (node (ref "R10") (pin "2") (pinfunction "2_2") (pintype "passive"))
      (node (ref "R11") (pin "1") (pinfunction "1_1") (pintype "passive"))
      (node (ref "R18") (pin "2") (pinfunction "2_2") (pintype "passive"))
      (node (ref "R19") (pin "1") (pinfunction "1_1") (pintype "passive"))
      (node (ref "R2") (pin "2") (pinfunction "2_2") (pintype "passive"))
    )
    (net (code "15") (name "Net-(R11-Pad2)") (class "Default")
      (node (ref "R11") (pin "2") (pinfunction "2_2") (pintype "passive"))
      (node (ref "R12") (pin "1") (pinfunction "1_1") (pintype "passive"))
      (node (ref "R19") (pin "2") (pinfunction "2_2") (pintype "passive"))
      (node (ref "R20") (pin "1") (pinfunction "1_1") (pintype "passive"))
      (node (ref "R3") (pin "2") (pinfunction "2_2") (pintype "passive"))
    )
    (net (code "16") (name "Net-(R12-Pad2)") (class "Default")
      (node (ref "R12") (pin "2") (pinfunction "2_2") (pintype "passive"))
      (node (ref "R15") (pin "1") (pinfunction "1_1") (pintype "passive"))
      (node (ref "R20") (pin "2") (pinfunction "2_2") (pintype "passive"))
      (node (ref "R24") (pin "1") (pinfunction "1_1") (pintype "passive"))
      (node (ref "R4") (pin "2") (pinfunction "2_2") (pintype "passive"))
    )
    (net (code "17") (name "Net-(R13-Pad1)") (class "Default")
      (node (ref "R13") (pin "1") (pinfunction "1_1") (pintype "passive"))
      (node (ref "R15") (pin "2") (pinfunction "2_2") (pintype "passive"))
      (node (ref "R21") (pin "1") (pinfunction "1_1") (pintype "passive"))
      (node (ref "R24") (pin "2") (pinfunction "2_2") (pintype "passive"))
      (node (ref "R5") (pin "2") (pinfunction "2_2") (pintype "passive"))
    )
    (net (code "18") (name "Net-(R13-Pad2)") (class "Default")
      (node (ref "R13") (pin "2") (pinfunction "2_2") (pintype "passive"))
      (node (ref "R16") (pin "1") (pinfunction "1_1") (pintype "passive"))
      (node (ref "R21") (pin "2") (pinfunction "2_2") (pintype "passive"))
      (node (ref "R25") (pin "1") (pinfunction "1_1") (pintype "passive"))
      (node (ref "R6") (pin "2") (pinfunction "2_2") (pintype "passive"))
    )
    (net (code "19") (name "Net-(R14-Pad1)") (class "Default")
      (node (ref "R14") (pin "1") (pinfunction "1_1") (pintype "passive"))
      (node (ref "R22") (pin "2") (pinfunction "2_2") (pintype "passive"))
      (node (ref "R23") (pin "1") (pinfunction "1_1") (pintype "passive"))
      (node (ref "R8") (pin "2") (pinfunction "2_2") (pintype "passive"))
      (node (ref "R9") (pin "2") (pinfunction "2_2") (pintype "passive"))
    )
    (net (code "20") (name "Net-(R16-Pad2)") (class "Default")
      (node (ref "R16") (pin "2") (pinfunction "2_2") (pintype "passive"))
      (node (ref "R17") (pin "1") (pinfunction "1_1") (pintype "passive"))
      (node (ref "R25") (pin "2") (pinfunction "2_2") (pintype "passive"))
      (node (ref "R7") (pin "2") (pinfunction "2_2") (pintype "passive"))
    )
    (net (code "21") (name "Net-(U1-GP0)") (class "Default")
      (node (ref "R8") (pin "1") (pinfunction "1_1") (pintype "passive"))
      (node (ref "U1") (pin "1") (pinfunction "GP0_1") (pintype "bidirectional"))
    )
    (net (code "22") (name "Net-(U1-GP1)") (class "Default")
      (node (ref "R1") (pin "1") (pinfunction "1_1") (pintype "passive"))
      (node (ref "U1") (pin "2") (pinfunction "GP1_2") (pintype "bidirectional"))
    )
    (net (code "23") (name "Net-(U1-GP2)") (class "Default")
      (node (ref "R2") (pin "1") (pinfunction "1_1") (pintype "passive"))
      (node (ref "U1") (pin "4") (pinfunction "GP2_4") (pintype "bidirectional"))
    )
    (net (code "24") (name "Net-(U1-GP3)") (class "Default")
      (node (ref "R3") (pin "1") (pinfunction "1_1") (pintype "passive"))
      (node (ref "U1") (pin "5") (pinfunction "GP3_5") (pintype "bidirectional"))
    )
    (net (code "25") (name "Net-(U1-GP4)") (class "Default")
      (node (ref "R4") (pin "1") (pinfunction "1_1") (pintype "passive"))
      (node (ref "U1") (pin "6") (pinfunction "GP4_6") (pintype "bidirectional"))
    )
    (net (code "26") (name "Net-(U1-GP5)") (class "Default")
      (node (ref "R5") (pin "1") (pinfunction "1_1") (pintype "passive"))
      (node (ref "U1") (pin "7") (pinfunction "GP5_7") (pintype "bidirectional"))
    )
    (net (code "27") (name "Net-(U1-GP6)") (class "Default")
      (node (ref "R6") (pin "1") (pinfunction "1_1") (pintype "passive"))
      (node (ref "U1") (pin "9") (pinfunction "GP6_9") (pintype "bidirectional"))
    )
    (net (code "28") (name "Net-(U1-GP7)") (class "Default")
      (node (ref "R7") (pin "1") (pinfunction "1_1") (pintype "passive"))
      (node (ref "U1") (pin "10") (pinfunction "GP7_10") (pintype "bidirectional"))
    )
    (net (code "29") (name "Net-(U2-BAL{slash}COMP3)") (class "Default")
      (node (ref "C2") (pin "1") (pinfunction "1_1") (pintype "passive"))
      (node (ref "U2") (pin "5") (pinfunction "BAL/COMP3_5") (pintype "passive"))
    )
    (net (code "30") (name "Net-(U2-IN+)") (class "Default")
      (node (ref "R26") (pin "1") (pinfunction "1_1") (pintype "passive"))
      (node (ref "R27") (pin "1") (pinfunction "1_1") (pintype "passive"))
      (node (ref "U2") (pin "3") (pinfunction "IN+_3") (pintype "tri_state"))
    )
    (net (code "31") (name "Net-(U2-IN-)") (class "Default")
      (node (ref "C5") (pin "1") (pinfunction "1_1") (pintype "passive"))
      (node (ref "R22") (pin "1") (pinfunction "1_1") (pintype "passive"))
      (node (ref "R28") (pin "1") (pinfunction "1_1") (pintype "passive"))
      (node (ref "R9") (pin "1") (pinfunction "1_1") (pintype "passive"))
      (node (ref "TP2") (pin "1") (pintype "input"))
      (node (ref "U2") (pin "2") (pinfunction "IN-_2") (pintype "tri_state"))
    )
    (net (code "32") (name "Net-(U2-OUT)") (class "Default")
      (node (ref "C11") (pin "1") (pinfunction "1_1") (pintype "passive"))
      (node (ref "C5") (pin "2") (pinfunction "2_2") (pintype "passive"))
      (node (ref "R28") (pin "2") (pinfunction "2_2") (pintype "passive"))
      (node (ref "TP4") (pin "1") (pintype "input"))
      (node (ref "U2") (pin "6") (pinfunction "OUT_6") (pintype "output"))
    )
    (net (code "33") (name "Net-(U3A-OUTA)") (class "Default")
      (node (ref "TP6") (pin "1") (pintype "input"))
      (node (ref "U3") (pin "7") (pinfunction "OUTA_7") (pintype "output"))
      (node (ref "U4") (pin "8") (pinfunction "SB_8") (pintype "passive"))
    )
    (net (code "34") (name "Net-(U4-D)") (class "Default")
      (node (ref "R29") (pin "1") (pinfunction "1_1") (pintype "passive"))
      (node (ref "R30") (pin "1") (pinfunction "1_1") (pintype "passive"))
      (node (ref "U4") (pin "1") (pinfunction "D_1") (pintype "passive"))
    )
    (net (code "35") (name "Net-(U5-IN-)") (class "Default")
      (node (ref "C16") (pin "1") (pinfunction "1_1") (pintype "passive"))
      (node (ref "R33") (pin "2") (pinfunction "2_2") (pintype "passive"))
      (node (ref "R34") (pin "1") (pinfunction "1_1") (pintype "passive"))
      (node (ref "U5") (pin "2") (pinfunction "IN-_2") (pintype "tri_state"))
    )
    (net (code "36") (name "Net-(U5-OUT)") (class "Default")
      (node (ref "C16") (pin "2") (pinfunction "2_2") (pintype "passive"))
      (node (ref "C20") (pin "1") (pinfunction "1_1") (pintype "passive"))
      (node (ref "R34") (pin "2") (pinfunction "2_2") (pintype "passive"))
      (node (ref "R34") (pin "3") (pinfunction "3_3") (pintype "passive"))
      (node (ref "U5") (pin "6") (pinfunction "OUT_6") (pintype "output"))
    )
    (net (code "37") (name "Net-(U6-IN+)") (class "Default")
      (node (ref "R37") (pin "2") (pinfunction "2_2") (pintype "passive"))
      (node (ref "U6") (pin "3") (pinfunction "IN+_3") (pintype "tri_state"))
    )
    (net (code "38") (name "Net-(U6-IN-)") (class "Default")
      (node (ref "C22") (pin "1") (pinfunction "1_1") (pintype "passive"))
      (node (ref "R36") (pin "2") (pinfunction "2_2") (pintype "passive"))
      (node (ref "R38") (pin "1") (pinfunction "1_1") (pintype "passive"))
      (node (ref "U6") (pin "2") (pinfunction "IN-_2") (pintype "tri_state"))
    )
    (net (code "39") (name "VCC") (class "Default")
      (node (ref "C1") (pin "1") (pinfunction "1_1") (pintype "passive"))
      (node (ref "C15") (pin "1") (pinfunction "1_1") (pintype "passive"))
      (node (ref "C17") (pin "2") (pinfunction "A_2") (pintype "passive"))
      (node (ref "C2") (pin "2") (pinfunction "2_2") (pintype "passive"))
      (node (ref "C21") (pin "1") (pinfunction "1_1") (pintype "passive"))
      (node (ref "C23") (pin "2") (pinfunction "A_2") (pintype "passive"))
      (node (ref "C26") (pin "2") (pinfunction "A_2") (pintype "passive"))
      (node (ref "C3") (pin "1") (pinfunction "1_1") (pintype "passive"))
      (node (ref "C4") (pin "2") (pinfunction "A_2") (pintype "passive"))
      (node (ref "C6") (pin "2") (pinfunction "A_2") (pintype "passive"))
      (node (ref "C9") (pin "1") (pinfunction "1_1") (pintype "passive"))
      (node (ref "DS2") (pin "1") (pinfunction "A_1") (pintype "passive"))
      (node (ref "J1") (pin "3") (pinfunction "3_3") (pintype "passive"))
      (node (ref "U2") (pin "7") (pinfunction "VCC+_7") (pintype "power_in"))
      (node (ref "U3") (pin "6") (pinfunction "VDD_6") (pintype "power_in"))
      (node (ref "U4") (pin "4") (pinfunction "VDD_4") (pintype "power_in"))
      (node (ref "U4") (pin "5") (pinfunction "EN_5") (pintype "input"))
      (node (ref "U5") (pin "7") (pinfunction "VCC+_7") (pintype "power_in"))
      (node (ref "U6") (pin "7") (pinfunction "VCC+_7") (pintype "power_in"))
    )
    (net (code "40") (name "VEE") (class "Default")
      (node (ref "C10") (pin "1") (pinfunction "1_1") (pintype "passive"))
      (node (ref "C18") (pin "1") (pinfunction "1_1") (pintype "passive"))
      (node (ref "C19") (pin "1") (pinfunction "C_1") (pintype "passive"))
      (node (ref "C24") (pin "1") (pinfunction "1_1") (pintype "passive"))
      (node (ref "C25") (pin "1") (pinfunction "C_1") (pintype "passive"))
      (node (ref "C27") (pin "1") (pinfunction "C_1") (pintype "passive"))
      (node (ref "C7") (pin "1") (pinfunction "1_1") (pintype "passive"))
      (node (ref "C8") (pin "1") (pinfunction "C_1") (pintype "passive"))
      (node (ref "DS1") (pin "2") (pinfunction "K_2") (pintype "passive"))
      (node (ref "J1") (pin "1") (pinfunction "1_1") (pintype "passive"))
      (node (ref "U2") (pin "4") (pinfunction "VCC-_4") (pintype "power_in"))
      (node (ref "U4") (pin "7") (pinfunction "VSS_7") (pintype "power_in"))
      (node (ref "U4") (pin "9") (pinfunction "EP_9") (pintype "power_in"))
      (node (ref "U5") (pin "4") (pinfunction "VCC-_4") (pintype "power_in"))
      (node (ref "U6") (pin "4") (pinfunction "VCC-_4") (pintype "power_in"))
    )
    (net (code "41") (name "unconnected-(J2-MNT_1-Pad3)") (class "Default")
      (node (ref "J2") (pin "3") (pinfunction "MNT_1_3") (pintype "passive"))
    )
    (net (code "42") (name "unconnected-(J2-MNT_2-Pad4)") (class "Default")
      (node (ref "J2") (pin "4") (pinfunction "MNT_2_4") (pintype "passive"))
    )
    (net (code "43") (name "unconnected-(R34-MNT_1-Pad4)") (class "Default")
      (node (ref "R34") (pin "4") (pinfunction "MNT_1_4") (pintype "passive"))
    )
    (net (code "44") (name "unconnected-(R34-MNT_2-Pad5)") (class "Default")
      (node (ref "R34") (pin "5") (pinfunction "MNT_2_5") (pintype "passive"))
    )
    (net (code "45") (name "unconnected-(U1-3V3-Pad36)") (class "Default")
      (node (ref "U1") (pin "36") (pinfunction "3V3_36") (pintype "power_in"))
    )
    (net (code "46") (name "unconnected-(U1-AVREF-Pad35)") (class "Default")
      (node (ref "U1") (pin "35") (pinfunction "AVREF_35") (pintype "power_in+no_connect"))
    )
    (net (code "47") (name "unconnected-(U1-EN-Pad37)") (class "Default")
      (node (ref "U1") (pin "37") (pinfunction "EN_37") (pintype "input+no_connect"))
    )
    (net (code "48") (name "unconnected-(U1-GP8-Pad11)") (class "Default")
      (node (ref "U1") (pin "11") (pinfunction "GP8_11") (pintype "bidirectional+no_connect"))
    )
    (net (code "49") (name "unconnected-(U1-GP11-Pad15)") (class "Default")
      (node (ref "U1") (pin "15") (pinfunction "GP11_15") (pintype "bidirectional+no_connect"))
    )
    (net (code "50") (name "unconnected-(U1-GP12-Pad16)") (class "Default")
      (node (ref "U1") (pin "16") (pinfunction "GP12_16") (pintype "bidirectional+no_connect"))
    )
    (net (code "51") (name "unconnected-(U1-GP13-Pad17)") (class "Default")
      (node (ref "U1") (pin "17") (pinfunction "GP13_17") (pintype "bidirectional+no_connect"))
    )
    (net (code "52") (name "unconnected-(U1-GP14-Pad19)") (class "Default")
      (node (ref "U1") (pin "19") (pinfunction "GP14_19") (pintype "bidirectional+no_connect"))
    )
    (net (code "53") (name "unconnected-(U1-GP15-Pad20)") (class "Default")
      (node (ref "U1") (pin "20") (pinfunction "GP15_20") (pintype "bidirectional+no_connect"))
    )
    (net (code "54") (name "unconnected-(U1-GP16-Pad21)") (class "Default")
      (node (ref "U1") (pin "21") (pinfunction "GP16_21") (pintype "bidirectional+no_connect"))
    )
    (net (code "55") (name "unconnected-(U1-GP17-Pad22)") (class "Default")
      (node (ref "U1") (pin "22") (pinfunction "GP17_22") (pintype "bidirectional+no_connect"))
    )
    (net (code "56") (name "unconnected-(U1-GP18-Pad24)") (class "Default")
      (node (ref "U1") (pin "24") (pinfunction "GP18_24") (pintype "bidirectional+no_connect"))
    )
    (net (code "57") (name "unconnected-(U1-GP19-Pad25)") (class "Default")
      (node (ref "U1") (pin "25") (pinfunction "GP19_25") (pintype "bidirectional+no_connect"))
    )
    (net (code "58") (name "unconnected-(U1-GP20-Pad26)") (class "Default")
      (node (ref "U1") (pin "26") (pinfunction "GP20_26") (pintype "bidirectional+no_connect"))
    )
    (net (code "59") (name "unconnected-(U1-GP21-Pad27)") (class "Default")
      (node (ref "U1") (pin "27") (pinfunction "GP21_27") (pintype "bidirectional+no_connect"))
    )
    (net (code "60") (name "unconnected-(U1-GP22-Pad29)") (class "Default")
      (node (ref "U1") (pin "29") (pinfunction "GP22_29") (pintype "bidirectional+no_connect"))
    )
    (net (code "61") (name "unconnected-(U1-GP26-Pad31)") (class "Default")
      (node (ref "U1") (pin "31") (pinfunction "GP26_31") (pintype "bidirectional+no_connect"))
    )
    (net (code "62") (name "unconnected-(U1-GP27-Pad32)") (class "Default")
      (node (ref "U1") (pin "32") (pinfunction "GP27_32") (pintype "bidirectional+no_connect"))
    )
    (net (code "63") (name "unconnected-(U1-GP28-Pad34)") (class "Default")
      (node (ref "U1") (pin "34") (pinfunction "GP28_34") (pintype "bidirectional+no_connect"))
    )
    (net (code "64") (name "unconnected-(U1-RUN-Pad30)") (class "Default")
      (node (ref "U1") (pin "30") (pinfunction "RUN_30") (pintype "input+no_connect"))
    )
    (net (code "65") (name "unconnected-(U1-SWCLK-Pad41)") (class "Default")
      (node (ref "U1") (pin "41") (pinfunction "SWCLK_41") (pintype "bidirectional+no_connect"))
    )
    (net (code "66") (name "unconnected-(U1-SWDIO-Pad43)") (class "Default")
      (node (ref "U1") (pin "43") (pinfunction "SWDIO_43") (pintype "bidirectional+no_connect"))
    )
    (net (code "67") (name "unconnected-(U1-TP2{slash}USBDM-Pad45)") (class "Default")
      (node (ref "U1") (pin "45") (pinfunction "TP2/USBDM_45") (pintype "bidirectional+no_connect"))
    )
    (net (code "68") (name "unconnected-(U1-TP3{slash}USBDP-Pad46)") (class "Default")
      (node (ref "U1") (pin "46") (pinfunction "TP3/USBDP_46") (pintype "bidirectional+no_connect"))
    )
    (net (code "69") (name "unconnected-(U1-TP4{slash}PS-Pad47)") (class "Default")
      (node (ref "U1") (pin "47") (pinfunction "TP4/PS_47") (pintype "bidirectional+no_connect"))
    )
    (net (code "70") (name "unconnected-(U1-TP5{slash}LED-Pad48)") (class "Default")
      (node (ref "U1") (pin "48") (pinfunction "TP5/LED_48") (pintype "bidirectional+no_connect"))
    )
    (net (code "71") (name "unconnected-(U1-TP6{slash}BOOT-Pad49)") (class "Default")
      (node (ref "U1") (pin "49") (pinfunction "TP6/BOOT_49") (pintype "bidirectional+no_connect"))
    )
    (net (code "72") (name "unconnected-(U1-VBUS-Pad40)") (class "Default")
      (node (ref "U1") (pin "40") (pinfunction "VBUS_40") (pintype "power_in+no_connect"))
    )
    (net (code "73") (name "unconnected-(U1-VSYS-Pad39)") (class "Default")
      (node (ref "U1") (pin "39") (pinfunction "VSYS_39") (pintype "power_in+no_connect"))
    )
    (net (code "74") (name "unconnected-(U2-BAL{slash}COMP1-Pad1)") (class "Default")
      (node (ref "U2") (pin "1") (pinfunction "BAL/COMP1_1") (pintype "passive"))
    )
    (net (code "75") (name "unconnected-(U2-COMP2-Pad8)") (class "Default")
      (node (ref "U2") (pin "8") (pinfunction "COMP2_8") (pintype "passive"))
    )
    (net (code "76") (name "unconnected-(U3A-GND-Pad3)") (class "Default")
      (node (ref "U3") (pin "3") (pinfunction "GND_3") (pintype "power_in"))
    )
    (net (code "77") (name "unconnected-(U3A-VDD-Pad6)") (class "Default")
      (node (ref "U3") (pin "6") (pinfunction "VDD_6") (pintype "power_in"))
    )
    (net (code "78") (name "unconnected-(U3B-OUTB-Pad5)") (class "Default")
      (node (ref "U3") (pin "5") (pinfunction "OUTB_5") (pintype "output"))
    )
    (net (code "79") (name "unconnected-(U5-BAL{slash}COMP1-Pad1)") (class "Default")
      (node (ref "U5") (pin "1") (pinfunction "BAL/COMP1_1") (pintype "passive"))
    )
    (net (code "80") (name "unconnected-(U5-BAL{slash}COMP3-Pad5)") (class "Default")
      (node (ref "U5") (pin "5") (pinfunction "BAL/COMP3_5") (pintype "passive"))
    )
    (net (code "81") (name "unconnected-(U5-COMP2-Pad8)") (class "Default")
      (node (ref "U5") (pin "8") (pinfunction "COMP2_8") (pintype "passive"))
    )
    (net (code "82") (name "unconnected-(U6-BAL{slash}COMP1-Pad1)") (class "Default")
      (node (ref "U6") (pin "1") (pinfunction "BAL/COMP1_1") (pintype "passive"))
    )
    (net (code "83") (name "unconnected-(U6-BAL{slash}COMP3-Pad5)") (class "Default")
      (node (ref "U6") (pin "5") (pinfunction "BAL/COMP3_5") (pintype "passive"))
    )
    (net (code "84") (name "unconnected-(U6-COMP2-Pad8)") (class "Default")
      (node (ref "U6") (pin "8") (pinfunction "COMP2_8") (pintype "passive"))
    )
  )
)
